# 7seg_clock_ver3.net
KiCad netlist of a schematic drawn in EAGLE
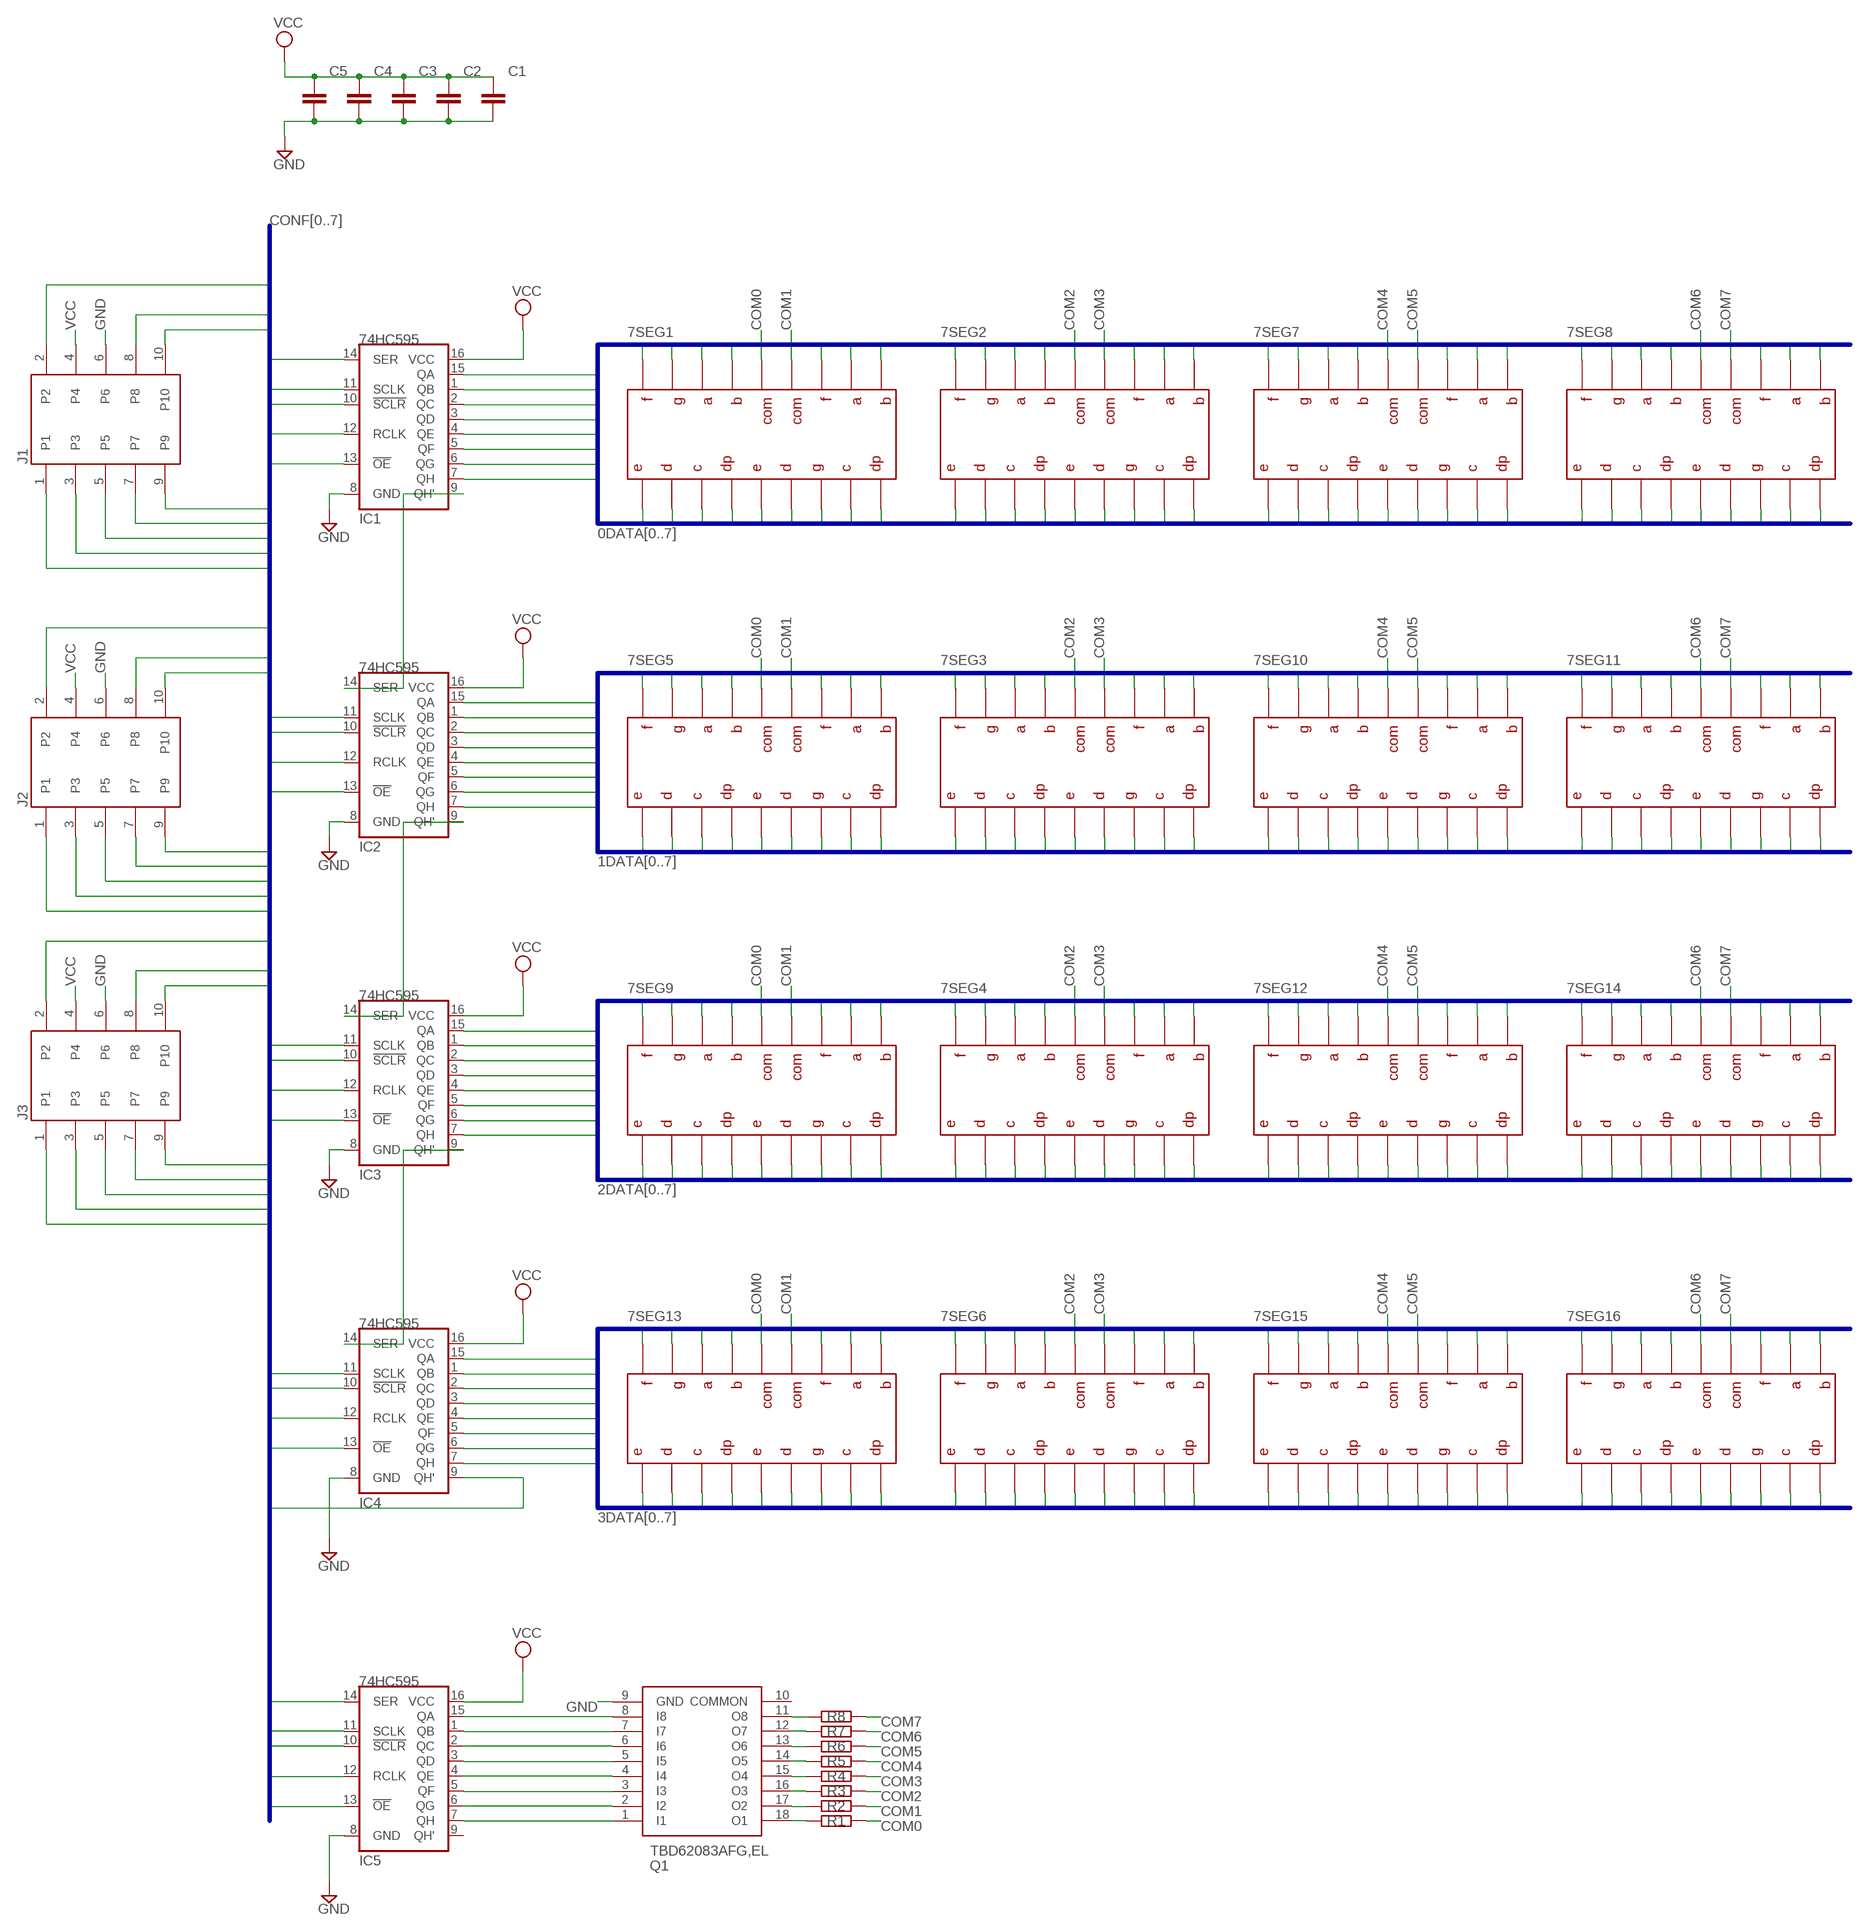
[diagram p0: schematic, sheet 1]

(export (version "E")
  (design (tool "Eeschema 10.0.6"))
  (components
    (comp (ref "7SEG1")
      (value "SL-3264")
      (footprint "eagle-import:SL-3264")
      (libsource (lib "eagle-import") (part "SL-3264"))
    )
    (comp (ref "7SEG2")
      (value "SL-3264")
      (footprint "eagle-import:SL-3264")
      (libsource (lib "eagle-import") (part "SL-3264"))
    )
    (comp (ref "7SEG3")
      (value "SL-3264")
      (footprint "eagle-import:SL-3264")
      (libsource (lib "eagle-import") (part "SL-3264"))
    )
    (comp (ref "7SEG4")
      (value "SL-3264")
      (footprint "eagle-import:SL-3264")
      (libsource (lib "eagle-import") (part "SL-3264"))
    )
    (comp (ref "7SEG5")
      (value "SL-3264")
      (footprint "eagle-import:SL-3264")
      (libsource (lib "eagle-import") (part "SL-3264"))
    )
    (comp (ref "7SEG6")
      (value "SL-3264")
      (footprint "eagle-import:SL-3264")
      (libsource (lib "eagle-import") (part "SL-3264"))
    )
    (comp (ref "7SEG7")
      (value "SL-3264")
      (footprint "eagle-import:SL-3264")
      (libsource (lib "eagle-import") (part "SL-3264"))
    )
    (comp (ref "7SEG8")
      (value "SL-3264")
      (footprint "eagle-import:SL-3264")
      (libsource (lib "eagle-import") (part "SL-3264"))
    )
    (comp (ref "7SEG9")
      (value "SL-3264")
      (footprint "eagle-import:SL-3264")
      (libsource (lib "eagle-import") (part "SL-3264"))
    )
    (comp (ref "7SEG10")
      (value "SL-3264")
      (footprint "eagle-import:SL-3264")
      (libsource (lib "eagle-import") (part "SL-3264"))
    )
    (comp (ref "7SEG11")
      (value "SL-3264")
      (footprint "eagle-import:SL-3264")
      (libsource (lib "eagle-import") (part "SL-3264"))
    )
    (comp (ref "7SEG12")
      (value "SL-3264")
      (footprint "eagle-import:SL-3264")
      (libsource (lib "eagle-import") (part "SL-3264"))
    )
    (comp (ref "7SEG13")
      (value "SL-3264")
      (footprint "eagle-import:SL-3264")
      (libsource (lib "eagle-import") (part "SL-3264"))
    )
    (comp (ref "7SEG14")
      (value "SL-3264")
      (footprint "eagle-import:SL-3264")
      (libsource (lib "eagle-import") (part "SL-3264"))
    )
    (comp (ref "7SEG15")
      (value "SL-3264")
      (footprint "eagle-import:SL-3264")
      (libsource (lib "eagle-import") (part "SL-3264"))
    )
    (comp (ref "7SEG16")
      (value "SL-3264")
      (footprint "eagle-import:SL-3264")
      (libsource (lib "eagle-import") (part "SL-3264"))
    )
    (comp (ref "C1")
      (value "C_CHIP-0603(1608-METRIC)")
      (footprint "eagle-import:CAPC1608X85")
      (libsource (lib "eagle-import") (part "CCHIP-0603(1608-METRIC)_"))
    )
    (comp (ref "C2")
      (value "C_CHIP-0603(1608-METRIC)")
      (footprint "eagle-import:CAPC1608X85")
      (libsource (lib "eagle-import") (part "CCHIP-0603(1608-METRIC)_"))
    )
    (comp (ref "C3")
      (value "C_CHIP-0603(1608-METRIC)")
      (footprint "eagle-import:CAPC1608X85")
      (libsource (lib "eagle-import") (part "CCHIP-0603(1608-METRIC)_"))
    )
    (comp (ref "C4")
      (value "C_CHIP-0603(1608-METRIC)")
      (footprint "eagle-import:CAPC1608X85")
      (libsource (lib "eagle-import") (part "CCHIP-0603(1608-METRIC)_"))
    )
    (comp (ref "C5")
      (value "C_CHIP-0603(1608-METRIC)")
      (footprint "eagle-import:CAPC1608X85")
      (libsource (lib "eagle-import") (part "CCHIP-0603(1608-METRIC)_"))
    )
    (comp (ref "IC1")
      (value "74HC595")
      (footprint "eagle-import:SO16")
      (fields (field (name "MF") "Nexperia"))
      (libsource (lib "eagle-import") (part "74HC595"))
    )
    (comp (ref "IC2")
      (value "74HC595")
      (footprint "eagle-import:SO16")
      (fields (field (name "MF") "Nexperia"))
      (libsource (lib "eagle-import") (part "74HC595"))
    )
    (comp (ref "IC3")
      (value "74HC595")
      (footprint "eagle-import:SO16")
      (fields (field (name "MF") "Nexperia"))
      (libsource (lib "eagle-import") (part "74HC595"))
    )
    (comp (ref "IC4")
      (value "74HC595")
      (footprint "eagle-import:SO16")
      (fields (field (name "MF") "Nexperia"))
      (libsource (lib "eagle-import") (part "74HC595"))
    )
    (comp (ref "IC5")
      (value "74HC595")
      (footprint "eagle-import:SO16")
      (fields (field (name "MF") "Nexperia"))
      (libsource (lib "eagle-import") (part "74HC595"))
    )
    (comp (ref "J1")
      (value "1241050-5")
      (footprint "eagle-import:TE_1241050-5")
      (fields (field (name "MF") "TE Connectivity"))
      (libsource (lib "eagle-import") (part "1241050-5"))
    )
    (comp (ref "J2")
      (value "1241050-5")
      (footprint "eagle-import:TE_1241050-5")
      (fields (field (name "MF") "TE Connectivity"))
      (libsource (lib "eagle-import") (part "1241050-5"))
    )
    (comp (ref "J3")
      (value "1241050-5")
      (footprint "eagle-import:TE_1241050-5")
      (fields (field (name "MF") "TE Connectivity"))
      (libsource (lib "eagle-import") (part "1241050-5"))
    )
    (comp (ref "Q1")
      (value "TBD62083AFG,EL")
      (footprint "eagle-import:SOIC127P1030X245-18N")
      (fields (field (name "MF") "Toshiba Semiconductor"))
      (libsource (lib "eagle-import") (part "TBD62083AFG,EL"))
    )
    (comp (ref "R1")
      (value "R_CHIP-0603(1608-METRIC)")
      (footprint "eagle-import:RESC1608X60")
      (libsource (lib "eagle-import") (part "RCHIP-0603(1608-METRIC)_"))
    )
    (comp (ref "R2")
      (value "R_CHIP-0603(1608-METRIC)")
      (footprint "eagle-import:RESC1608X60")
      (libsource (lib "eagle-import") (part "RCHIP-0603(1608-METRIC)_"))
    )
    (comp (ref "R3")
      (value "R_CHIP-0603(1608-METRIC)")
      (footprint "eagle-import:RESC1608X60")
      (libsource (lib "eagle-import") (part "RCHIP-0603(1608-METRIC)_"))
    )
    (comp (ref "R4")
      (value "R_CHIP-0603(1608-METRIC)")
      (footprint "eagle-import:RESC1608X60")
      (libsource (lib "eagle-import") (part "RCHIP-0603(1608-METRIC)_"))
    )
    (comp (ref "R5")
      (value "R_CHIP-0603(1608-METRIC)")
      (footprint "eagle-import:RESC1608X60")
      (libsource (lib "eagle-import") (part "RCHIP-0603(1608-METRIC)_"))
    )
    (comp (ref "R6")
      (value "R_CHIP-0603(1608-METRIC)")
      (footprint "eagle-import:RESC1608X60")
      (libsource (lib "eagle-import") (part "RCHIP-0603(1608-METRIC)_"))
    )
    (comp (ref "R7")
      (value "R_CHIP-0603(1608-METRIC)")
      (footprint "eagle-import:RESC1608X60")
      (libsource (lib "eagle-import") (part "RCHIP-0603(1608-METRIC)_"))
    )
    (comp (ref "R8")
      (value "R_CHIP-0603(1608-METRIC)")
      (footprint "eagle-import:RESC1608X60")
      (libsource (lib "eagle-import") (part "RCHIP-0603(1608-METRIC)_"))
    )
  )
  (nets
    (net (code "1") (name "/0DATA0") (class "Default")
      (node (ref "7SEG1") (pin "P$10") (pinfunction "P$10_P$10") (pintype "bidirectional"))
      (node (ref "7SEG1") (pin "P$15") (pinfunction "P$15_P$15") (pintype "bidirectional"))
      (node (ref "7SEG2") (pin "P$10") (pinfunction "P$10_P$10") (pintype "bidirectional"))
      (node (ref "7SEG2") (pin "P$15") (pinfunction "P$15_P$15") (pintype "bidirectional"))
      (node (ref "7SEG7") (pin "P$10") (pinfunction "P$10_P$10") (pintype "bidirectional"))
      (node (ref "7SEG7") (pin "P$15") (pinfunction "P$15_P$15") (pintype "bidirectional"))
      (node (ref "7SEG8") (pin "P$10") (pinfunction "P$10_P$10") (pintype "bidirectional"))
      (node (ref "7SEG8") (pin "P$15") (pinfunction "P$15_P$15") (pintype "bidirectional"))
      (node (ref "IC1") (pin "15") (pinfunction "QA_15") (pintype "tri_state"))
    )
    (net (code "2") (name "/0DATA1") (class "Default")
      (node (ref "7SEG1") (pin "P$12") (pinfunction "P$12_P$12") (pintype "bidirectional"))
      (node (ref "7SEG1") (pin "P$18") (pinfunction "P$18_P$18") (pintype "bidirectional"))
      (node (ref "7SEG2") (pin "P$12") (pinfunction "P$12_P$12") (pintype "bidirectional"))
      (node (ref "7SEG2") (pin "P$18") (pinfunction "P$18_P$18") (pintype "bidirectional"))
      (node (ref "7SEG7") (pin "P$12") (pinfunction "P$12_P$12") (pintype "bidirectional"))
      (node (ref "7SEG7") (pin "P$18") (pinfunction "P$18_P$18") (pintype "bidirectional"))
      (node (ref "7SEG8") (pin "P$12") (pinfunction "P$12_P$12") (pintype "bidirectional"))
      (node (ref "7SEG8") (pin "P$18") (pinfunction "P$18_P$18") (pintype "bidirectional"))
      (node (ref "IC1") (pin "1") (pinfunction "QB_1") (pintype "tri_state"))
    )
    (net (code "3") (name "/0DATA2") (class "Default")
      (node (ref "7SEG1") (pin "P$17") (pinfunction "P$17_P$17") (pintype "bidirectional"))
      (node (ref "7SEG1") (pin "P$7") (pinfunction "P$7_P$7") (pintype "bidirectional"))
      (node (ref "7SEG2") (pin "P$17") (pinfunction "P$17_P$17") (pintype "bidirectional"))
      (node (ref "7SEG2") (pin "P$7") (pinfunction "P$7_P$7") (pintype "bidirectional"))
      (node (ref "7SEG7") (pin "P$17") (pinfunction "P$17_P$17") (pintype "bidirectional"))
      (node (ref "7SEG7") (pin "P$7") (pinfunction "P$7_P$7") (pintype "bidirectional"))
      (node (ref "7SEG8") (pin "P$17") (pinfunction "P$17_P$17") (pintype "bidirectional"))
      (node (ref "7SEG8") (pin "P$7") (pinfunction "P$7_P$7") (pintype "bidirectional"))
      (node (ref "IC1") (pin "2") (pinfunction "QC_2") (pintype "tri_state"))
    )
    (net (code "4") (name "/0DATA3") (class "Default")
      (node (ref "7SEG1") (pin "P$11") (pinfunction "P$11_P$11") (pintype "bidirectional"))
      (node (ref "7SEG1") (pin "P$16") (pinfunction "P$16_P$16") (pintype "bidirectional"))
      (node (ref "7SEG2") (pin "P$11") (pinfunction "P$11_P$11") (pintype "bidirectional"))
      (node (ref "7SEG2") (pin "P$16") (pinfunction "P$16_P$16") (pintype "bidirectional"))
      (node (ref "7SEG7") (pin "P$11") (pinfunction "P$11_P$11") (pintype "bidirectional"))
      (node (ref "7SEG7") (pin "P$16") (pinfunction "P$16_P$16") (pintype "bidirectional"))
      (node (ref "7SEG8") (pin "P$11") (pinfunction "P$11_P$11") (pintype "bidirectional"))
      (node (ref "7SEG8") (pin "P$16") (pinfunction "P$16_P$16") (pintype "bidirectional"))
      (node (ref "IC1") (pin "3") (pinfunction "QD_3") (pintype "tri_state"))
    )
    (net (code "5") (name "/0DATA4") (class "Default")
      (node (ref "7SEG1") (pin "P$4") (pinfunction "P$4_P$4") (pintype "bidirectional"))
      (node (ref "7SEG1") (pin "P$9") (pinfunction "P$9_P$9") (pintype "bidirectional"))
      (node (ref "7SEG2") (pin "P$4") (pinfunction "P$4_P$4") (pintype "bidirectional"))
      (node (ref "7SEG2") (pin "P$9") (pinfunction "P$9_P$9") (pintype "bidirectional"))
      (node (ref "7SEG7") (pin "P$4") (pinfunction "P$4_P$4") (pintype "bidirectional"))
      (node (ref "7SEG7") (pin "P$9") (pinfunction "P$9_P$9") (pintype "bidirectional"))
      (node (ref "7SEG8") (pin "P$4") (pinfunction "P$4_P$4") (pintype "bidirectional"))
      (node (ref "7SEG8") (pin "P$9") (pinfunction "P$9_P$9") (pintype "bidirectional"))
      (node (ref "IC1") (pin "4") (pinfunction "QE_4") (pintype "tri_state"))
    )
    (net (code "6") (name "/0DATA5") (class "Default")
      (node (ref "7SEG1") (pin "P$3") (pinfunction "P$3_P$3") (pintype "bidirectional"))
      (node (ref "7SEG1") (pin "P$8") (pinfunction "P$8_P$8") (pintype "bidirectional"))
      (node (ref "7SEG2") (pin "P$3") (pinfunction "P$3_P$3") (pintype "bidirectional"))
      (node (ref "7SEG2") (pin "P$8") (pinfunction "P$8_P$8") (pintype "bidirectional"))
      (node (ref "7SEG7") (pin "P$3") (pinfunction "P$3_P$3") (pintype "bidirectional"))
      (node (ref "7SEG7") (pin "P$8") (pinfunction "P$8_P$8") (pintype "bidirectional"))
      (node (ref "7SEG8") (pin "P$3") (pinfunction "P$3_P$3") (pintype "bidirectional"))
      (node (ref "7SEG8") (pin "P$8") (pinfunction "P$8_P$8") (pintype "bidirectional"))
      (node (ref "IC1") (pin "5") (pinfunction "QF_5") (pintype "tri_state"))
    )
    (net (code "7") (name "/0DATA6") (class "Default")
      (node (ref "7SEG1") (pin "P$2") (pinfunction "P$2_P$2") (pintype "bidirectional"))
      (node (ref "7SEG1") (pin "P$6") (pinfunction "P$6_P$6") (pintype "bidirectional"))
      (node (ref "7SEG2") (pin "P$2") (pinfunction "P$2_P$2") (pintype "bidirectional"))
      (node (ref "7SEG2") (pin "P$6") (pinfunction "P$6_P$6") (pintype "bidirectional"))
      (node (ref "7SEG7") (pin "P$2") (pinfunction "P$2_P$2") (pintype "bidirectional"))
      (node (ref "7SEG7") (pin "P$6") (pinfunction "P$6_P$6") (pintype "bidirectional"))
      (node (ref "7SEG8") (pin "P$2") (pinfunction "P$2_P$2") (pintype "bidirectional"))
      (node (ref "7SEG8") (pin "P$6") (pinfunction "P$6_P$6") (pintype "bidirectional"))
      (node (ref "IC1") (pin "6") (pinfunction "QG_6") (pintype "tri_state"))
    )
    (net (code "8") (name "/0DATA7") (class "Default")
      (node (ref "7SEG1") (pin "P$1") (pinfunction "P$1_P$1") (pintype "bidirectional"))
      (node (ref "7SEG1") (pin "P$5") (pinfunction "P$5_P$5") (pintype "bidirectional"))
      (node (ref "7SEG2") (pin "P$1") (pinfunction "P$1_P$1") (pintype "bidirectional"))
      (node (ref "7SEG2") (pin "P$5") (pinfunction "P$5_P$5") (pintype "bidirectional"))
      (node (ref "7SEG7") (pin "P$1") (pinfunction "P$1_P$1") (pintype "bidirectional"))
      (node (ref "7SEG7") (pin "P$5") (pinfunction "P$5_P$5") (pintype "bidirectional"))
      (node (ref "7SEG8") (pin "P$1") (pinfunction "P$1_P$1") (pintype "bidirectional"))
      (node (ref "7SEG8") (pin "P$5") (pinfunction "P$5_P$5") (pintype "bidirectional"))
      (node (ref "IC1") (pin "7") (pinfunction "QH_7") (pintype "tri_state"))
    )
    (net (code "10") (name "/1DATA0") (class "Default")
      (node (ref "7SEG10") (pin "P$10") (pinfunction "P$10_P$10") (pintype "bidirectional"))
      (node (ref "7SEG10") (pin "P$15") (pinfunction "P$15_P$15") (pintype "bidirectional"))
      (node (ref "7SEG11") (pin "P$10") (pinfunction "P$10_P$10") (pintype "bidirectional"))
      (node (ref "7SEG11") (pin "P$15") (pinfunction "P$15_P$15") (pintype "bidirectional"))
      (node (ref "7SEG3") (pin "P$10") (pinfunction "P$10_P$10") (pintype "bidirectional"))
      (node (ref "7SEG3") (pin "P$15") (pinfunction "P$15_P$15") (pintype "bidirectional"))
      (node (ref "7SEG5") (pin "P$10") (pinfunction "P$10_P$10") (pintype "bidirectional"))
      (node (ref "7SEG5") (pin "P$15") (pinfunction "P$15_P$15") (pintype "bidirectional"))
      (node (ref "IC2") (pin "15") (pinfunction "QA_15") (pintype "tri_state"))
    )
    (net (code "11") (name "/1DATA1") (class "Default")
      (node (ref "7SEG10") (pin "P$12") (pinfunction "P$12_P$12") (pintype "bidirectional"))
      (node (ref "7SEG10") (pin "P$18") (pinfunction "P$18_P$18") (pintype "bidirectional"))
      (node (ref "7SEG11") (pin "P$12") (pinfunction "P$12_P$12") (pintype "bidirectional"))
      (node (ref "7SEG11") (pin "P$18") (pinfunction "P$18_P$18") (pintype "bidirectional"))
      (node (ref "7SEG3") (pin "P$12") (pinfunction "P$12_P$12") (pintype "bidirectional"))
      (node (ref "7SEG3") (pin "P$18") (pinfunction "P$18_P$18") (pintype "bidirectional"))
      (node (ref "7SEG5") (pin "P$12") (pinfunction "P$12_P$12") (pintype "bidirectional"))
      (node (ref "7SEG5") (pin "P$18") (pinfunction "P$18_P$18") (pintype "bidirectional"))
      (node (ref "IC2") (pin "1") (pinfunction "QB_1") (pintype "tri_state"))
    )
    (net (code "12") (name "/1DATA2") (class "Default")
      (node (ref "7SEG10") (pin "P$17") (pinfunction "P$17_P$17") (pintype "bidirectional"))
      (node (ref "7SEG10") (pin "P$7") (pinfunction "P$7_P$7") (pintype "bidirectional"))
      (node (ref "7SEG11") (pin "P$17") (pinfunction "P$17_P$17") (pintype "bidirectional"))
      (node (ref "7SEG11") (pin "P$7") (pinfunction "P$7_P$7") (pintype "bidirectional"))
      (node (ref "7SEG3") (pin "P$17") (pinfunction "P$17_P$17") (pintype "bidirectional"))
      (node (ref "7SEG3") (pin "P$7") (pinfunction "P$7_P$7") (pintype "bidirectional"))
      (node (ref "7SEG5") (pin "P$17") (pinfunction "P$17_P$17") (pintype "bidirectional"))
      (node (ref "7SEG5") (pin "P$7") (pinfunction "P$7_P$7") (pintype "bidirectional"))
      (node (ref "IC2") (pin "2") (pinfunction "QC_2") (pintype "tri_state"))
    )
    (net (code "13") (name "/1DATA3") (class "Default")
      (node (ref "7SEG10") (pin "P$11") (pinfunction "P$11_P$11") (pintype "bidirectional"))
      (node (ref "7SEG10") (pin "P$16") (pinfunction "P$16_P$16") (pintype "bidirectional"))
      (node (ref "7SEG11") (pin "P$11") (pinfunction "P$11_P$11") (pintype "bidirectional"))
      (node (ref "7SEG11") (pin "P$16") (pinfunction "P$16_P$16") (pintype "bidirectional"))
      (node (ref "7SEG3") (pin "P$11") (pinfunction "P$11_P$11") (pintype "bidirectional"))
      (node (ref "7SEG3") (pin "P$16") (pinfunction "P$16_P$16") (pintype "bidirectional"))
      (node (ref "7SEG5") (pin "P$11") (pinfunction "P$11_P$11") (pintype "bidirectional"))
      (node (ref "7SEG5") (pin "P$16") (pinfunction "P$16_P$16") (pintype "bidirectional"))
      (node (ref "IC2") (pin "3") (pinfunction "QD_3") (pintype "tri_state"))
    )
    (net (code "14") (name "/1DATA4") (class "Default")
      (node (ref "7SEG10") (pin "P$4") (pinfunction "P$4_P$4") (pintype "bidirectional"))
      (node (ref "7SEG10") (pin "P$9") (pinfunction "P$9_P$9") (pintype "bidirectional"))
      (node (ref "7SEG11") (pin "P$4") (pinfunction "P$4_P$4") (pintype "bidirectional"))
      (node (ref "7SEG11") (pin "P$9") (pinfunction "P$9_P$9") (pintype "bidirectional"))
      (node (ref "7SEG3") (pin "P$4") (pinfunction "P$4_P$4") (pintype "bidirectional"))
      (node (ref "7SEG3") (pin "P$9") (pinfunction "P$9_P$9") (pintype "bidirectional"))
      (node (ref "7SEG5") (pin "P$4") (pinfunction "P$4_P$4") (pintype "bidirectional"))
      (node (ref "7SEG5") (pin "P$9") (pinfunction "P$9_P$9") (pintype "bidirectional"))
      (node (ref "IC2") (pin "4") (pinfunction "QE_4") (pintype "tri_state"))
    )
    (net (code "15") (name "/1DATA5") (class "Default")
      (node (ref "7SEG10") (pin "P$3") (pinfunction "P$3_P$3") (pintype "bidirectional"))
      (node (ref "7SEG10") (pin "P$8") (pinfunction "P$8_P$8") (pintype "bidirectional"))
      (node (ref "7SEG11") (pin "P$3") (pinfunction "P$3_P$3") (pintype "bidirectional"))
      (node (ref "7SEG11") (pin "P$8") (pinfunction "P$8_P$8") (pintype "bidirectional"))
      (node (ref "7SEG3") (pin "P$3") (pinfunction "P$3_P$3") (pintype "bidirectional"))
      (node (ref "7SEG3") (pin "P$8") (pinfunction "P$8_P$8") (pintype "bidirectional"))
      (node (ref "7SEG5") (pin "P$3") (pinfunction "P$3_P$3") (pintype "bidirectional"))
      (node (ref "7SEG5") (pin "P$8") (pinfunction "P$8_P$8") (pintype "bidirectional"))
      (node (ref "IC2") (pin "5") (pinfunction "QF_5") (pintype "tri_state"))
    )
    (net (code "16") (name "/1DATA6") (class "Default")
      (node (ref "7SEG10") (pin "P$2") (pinfunction "P$2_P$2") (pintype "bidirectional"))
      (node (ref "7SEG10") (pin "P$6") (pinfunction "P$6_P$6") (pintype "bidirectional"))
      (node (ref "7SEG11") (pin "P$2") (pinfunction "P$2_P$2") (pintype "bidirectional"))
      (node (ref "7SEG11") (pin "P$6") (pinfunction "P$6_P$6") (pintype "bidirectional"))
      (node (ref "7SEG3") (pin "P$2") (pinfunction "P$2_P$2") (pintype "bidirectional"))
      (node (ref "7SEG3") (pin "P$6") (pinfunction "P$6_P$6") (pintype "bidirectional"))
      (node (ref "7SEG5") (pin "P$2") (pinfunction "P$2_P$2") (pintype "bidirectional"))
      (node (ref "7SEG5") (pin "P$6") (pinfunction "P$6_P$6") (pintype "bidirectional"))
      (node (ref "IC2") (pin "6") (pinfunction "QG_6") (pintype "tri_state"))
    )
    (net (code "17") (name "/1DATA7") (class "Default")
      (node (ref "7SEG10") (pin "P$1") (pinfunction "P$1_P$1") (pintype "bidirectional"))
      (node (ref "7SEG10") (pin "P$5") (pinfunction "P$5_P$5") (pintype "bidirectional"))
      (node (ref "7SEG11") (pin "P$1") (pinfunction "P$1_P$1") (pintype "bidirectional"))
      (node (ref "7SEG11") (pin "P$5") (pinfunction "P$5_P$5") (pintype "bidirectional"))
      (node (ref "7SEG3") (pin "P$1") (pinfunction "P$1_P$1") (pintype "bidirectional"))
      (node (ref "7SEG3") (pin "P$5") (pinfunction "P$5_P$5") (pintype "bidirectional"))
      (node (ref "7SEG5") (pin "P$1") (pinfunction "P$1_P$1") (pintype "bidirectional"))
      (node (ref "7SEG5") (pin "P$5") (pinfunction "P$5_P$5") (pintype "bidirectional"))
      (node (ref "IC2") (pin "7") (pinfunction "QH_7") (pintype "tri_state"))
    )
    (net (code "19") (name "/2DATA0") (class "Default")
      (node (ref "7SEG12") (pin "P$10") (pinfunction "P$10_P$10") (pintype "bidirectional"))
      (node (ref "7SEG12") (pin "P$15") (pinfunction "P$15_P$15") (pintype "bidirectional"))
      (node (ref "7SEG14") (pin "P$10") (pinfunction "P$10_P$10") (pintype "bidirectional"))
      (node (ref "7SEG14") (pin "P$15") (pinfunction "P$15_P$15") (pintype "bidirectional"))
      (node (ref "7SEG4") (pin "P$10") (pinfunction "P$10_P$10") (pintype "bidirectional"))
      (node (ref "7SEG4") (pin "P$15") (pinfunction "P$15_P$15") (pintype "bidirectional"))
      (node (ref "7SEG9") (pin "P$10") (pinfunction "P$10_P$10") (pintype "bidirectional"))
      (node (ref "7SEG9") (pin "P$15") (pinfunction "P$15_P$15") (pintype "bidirectional"))
      (node (ref "IC3") (pin "15") (pinfunction "QA_15") (pintype "tri_state"))
    )
    (net (code "20") (name "/2DATA1") (class "Default")
      (node (ref "7SEG12") (pin "P$12") (pinfunction "P$12_P$12") (pintype "bidirectional"))
      (node (ref "7SEG12") (pin "P$18") (pinfunction "P$18_P$18") (pintype "bidirectional"))
      (node (ref "7SEG14") (pin "P$12") (pinfunction "P$12_P$12") (pintype "bidirectional"))
      (node (ref "7SEG14") (pin "P$18") (pinfunction "P$18_P$18") (pintype "bidirectional"))
      (node (ref "7SEG4") (pin "P$12") (pinfunction "P$12_P$12") (pintype "bidirectional"))
      (node (ref "7SEG4") (pin "P$18") (pinfunction "P$18_P$18") (pintype "bidirectional"))
      (node (ref "7SEG9") (pin "P$12") (pinfunction "P$12_P$12") (pintype "bidirectional"))
      (node (ref "7SEG9") (pin "P$18") (pinfunction "P$18_P$18") (pintype "bidirectional"))
      (node (ref "IC3") (pin "1") (pinfunction "QB_1") (pintype "tri_state"))
    )
    (net (code "21") (name "/2DATA2") (class "Default")
      (node (ref "7SEG12") (pin "P$17") (pinfunction "P$17_P$17") (pintype "bidirectional"))
      (node (ref "7SEG12") (pin "P$7") (pinfunction "P$7_P$7") (pintype "bidirectional"))
      (node (ref "7SEG14") (pin "P$17") (pinfunction "P$17_P$17") (pintype "bidirectional"))
      (node (ref "7SEG14") (pin "P$7") (pinfunction "P$7_P$7") (pintype "bidirectional"))
      (node (ref "7SEG4") (pin "P$17") (pinfunction "P$17_P$17") (pintype "bidirectional"))
      (node (ref "7SEG4") (pin "P$7") (pinfunction "P$7_P$7") (pintype "bidirectional"))
      (node (ref "7SEG9") (pin "P$17") (pinfunction "P$17_P$17") (pintype "bidirectional"))
      (node (ref "7SEG9") (pin "P$7") (pinfunction "P$7_P$7") (pintype "bidirectional"))
      (node (ref "IC3") (pin "2") (pinfunction "QC_2") (pintype "tri_state"))
    )
    (net (code "22") (name "/2DATA3") (class "Default")
      (node (ref "7SEG12") (pin "P$11") (pinfunction "P$11_P$11") (pintype "bidirectional"))
      (node (ref "7SEG12") (pin "P$16") (pinfunction "P$16_P$16") (pintype "bidirectional"))
      (node (ref "7SEG14") (pin "P$11") (pinfunction "P$11_P$11") (pintype "bidirectional"))
      (node (ref "7SEG14") (pin "P$16") (pinfunction "P$16_P$16") (pintype "bidirectional"))
      (node (ref "7SEG4") (pin "P$11") (pinfunction "P$11_P$11") (pintype "bidirectional"))
      (node (ref "7SEG4") (pin "P$16") (pinfunction "P$16_P$16") (pintype "bidirectional"))
      (node (ref "7SEG9") (pin "P$11") (pinfunction "P$11_P$11") (pintype "bidirectional"))
      (node (ref "7SEG9") (pin "P$16") (pinfunction "P$16_P$16") (pintype "bidirectional"))
      (node (ref "IC3") (pin "3") (pinfunction "QD_3") (pintype "tri_state"))
    )
    (net (code "23") (name "/2DATA4") (class "Default")
      (node (ref "7SEG12") (pin "P$4") (pinfunction "P$4_P$4") (pintype "bidirectional"))
      (node (ref "7SEG12") (pin "P$9") (pinfunction "P$9_P$9") (pintype "bidirectional"))
      (node (ref "7SEG14") (pin "P$4") (pinfunction "P$4_P$4") (pintype "bidirectional"))
      (node (ref "7SEG14") (pin "P$9") (pinfunction "P$9_P$9") (pintype "bidirectional"))
      (node (ref "7SEG4") (pin "P$4") (pinfunction "P$4_P$4") (pintype "bidirectional"))
      (node (ref "7SEG4") (pin "P$9") (pinfunction "P$9_P$9") (pintype "bidirectional"))
      (node (ref "7SEG9") (pin "P$4") (pinfunction "P$4_P$4") (pintype "bidirectional"))
      (node (ref "7SEG9") (pin "P$9") (pinfunction "P$9_P$9") (pintype "bidirectional"))
      (node (ref "IC3") (pin "4") (pinfunction "QE_4") (pintype "tri_state"))
    )
    (net (code "24") (name "/2DATA5") (class "Default")
      (node (ref "7SEG12") (pin "P$3") (pinfunction "P$3_P$3") (pintype "bidirectional"))
      (node (ref "7SEG12") (pin "P$8") (pinfunction "P$8_P$8") (pintype "bidirectional"))
      (node (ref "7SEG14") (pin "P$3") (pinfunction "P$3_P$3") (pintype "bidirectional"))
      (node (ref "7SEG14") (pin "P$8") (pinfunction "P$8_P$8") (pintype "bidirectional"))
      (node (ref "7SEG4") (pin "P$3") (pinfunction "P$3_P$3") (pintype "bidirectional"))
      (node (ref "7SEG4") (pin "P$8") (pinfunction "P$8_P$8") (pintype "bidirectional"))
      (node (ref "7SEG9") (pin "P$3") (pinfunction "P$3_P$3") (pintype "bidirectional"))
      (node (ref "7SEG9") (pin "P$8") (pinfunction "P$8_P$8") (pintype "bidirectional"))
      (node (ref "IC3") (pin "5") (pinfunction "QF_5") (pintype "tri_state"))
    )
    (net (code "25") (name "/2DATA6") (class "Default")
      (node (ref "7SEG12") (pin "P$2") (pinfunction "P$2_P$2") (pintype "bidirectional"))
      (node (ref "7SEG12") (pin "P$6") (pinfunction "P$6_P$6") (pintype "bidirectional"))
      (node (ref "7SEG14") (pin "P$2") (pinfunction "P$2_P$2") (pintype "bidirectional"))
      (node (ref "7SEG14") (pin "P$6") (pinfunction "P$6_P$6") (pintype "bidirectional"))
      (node (ref "7SEG4") (pin "P$2") (pinfunction "P$2_P$2") (pintype "bidirectional"))
      (node (ref "7SEG4") (pin "P$6") (pinfunction "P$6_P$6") (pintype "bidirectional"))
      (node (ref "7SEG9") (pin "P$2") (pinfunction "P$2_P$2") (pintype "bidirectional"))
      (node (ref "7SEG9") (pin "P$6") (pinfunction "P$6_P$6") (pintype "bidirectional"))
      (node (ref "IC3") (pin "6") (pinfunction "QG_6") (pintype "tri_state"))
    )
    (net (code "26") (name "/2DATA7") (class "Default")
      (node (ref "7SEG12") (pin "P$1") (pinfunction "P$1_P$1") (pintype "bidirectional"))
      (node (ref "7SEG12") (pin "P$5") (pinfunction "P$5_P$5") (pintype "bidirectional"))
      (node (ref "7SEG14") (pin "P$1") (pinfunction "P$1_P$1") (pintype "bidirectional"))
      (node (ref "7SEG14") (pin "P$5") (pinfunction "P$5_P$5") (pintype "bidirectional"))
      (node (ref "7SEG4") (pin "P$1") (pinfunction "P$1_P$1") (pintype "bidirectional"))
      (node (ref "7SEG4") (pin "P$5") (pinfunction "P$5_P$5") (pintype "bidirectional"))
      (node (ref "7SEG9") (pin "P$1") (pinfunction "P$1_P$1") (pintype "bidirectional"))
      (node (ref "7SEG9") (pin "P$5") (pinfunction "P$5_P$5") (pintype "bidirectional"))
      (node (ref "IC3") (pin "7") (pinfunction "QH_7") (pintype "tri_state"))
    )
    (net (code "28") (name "/3DATA0") (class "Default")
      (node (ref "7SEG13") (pin "P$10") (pinfunction "P$10_P$10") (pintype "bidirectional"))
      (node (ref "7SEG13") (pin "P$15") (pinfunction "P$15_P$15") (pintype "bidirectional"))
      (node (ref "7SEG15") (pin "P$10") (pinfunction "P$10_P$10") (pintype "bidirectional"))
      (node (ref "7SEG15") (pin "P$15") (pinfunction "P$15_P$15") (pintype "bidirectional"))
      (node (ref "7SEG16") (pin "P$10") (pinfunction "P$10_P$10") (pintype "bidirectional"))
      (node (ref "7SEG16") (pin "P$15") (pinfunction "P$15_P$15") (pintype "bidirectional"))
      (node (ref "7SEG6") (pin "P$10") (pinfunction "P$10_P$10") (pintype "bidirectional"))
      (node (ref "7SEG6") (pin "P$15") (pinfunction "P$15_P$15") (pintype "bidirectional"))
      (node (ref "IC4") (pin "15") (pinfunction "QA_15") (pintype "tri_state"))
    )
    (net (code "29") (name "/3DATA1") (class "Default")
      (node (ref "7SEG13") (pin "P$12") (pinfunction "P$12_P$12") (pintype "bidirectional"))
      (node (ref "7SEG13") (pin "P$18") (pinfunction "P$18_P$18") (pintype "bidirectional"))
      (node (ref "7SEG15") (pin "P$12") (pinfunction "P$12_P$12") (pintype "bidirectional"))
      (node (ref "7SEG15") (pin "P$18") (pinfunction "P$18_P$18") (pintype "bidirectional"))
      (node (ref "7SEG16") (pin "P$12") (pinfunction "P$12_P$12") (pintype "bidirectional"))
      (node (ref "7SEG16") (pin "P$18") (pinfunction "P$18_P$18") (pintype "bidirectional"))
      (node (ref "7SEG6") (pin "P$12") (pinfunction "P$12_P$12") (pintype "bidirectional"))
      (node (ref "7SEG6") (pin "P$18") (pinfunction "P$18_P$18") (pintype "bidirectional"))
      (node (ref "IC4") (pin "1") (pinfunction "QB_1") (pintype "tri_state"))
    )
    (net (code "30") (name "/3DATA2") (class "Default")
      (node (ref "7SEG13") (pin "P$17") (pinfunction "P$17_P$17") (pintype "bidirectional"))
      (node (ref "7SEG13") (pin "P$7") (pinfunction "P$7_P$7") (pintype "bidirectional"))
      (node (ref "7SEG15") (pin "P$17") (pinfunction "P$17_P$17") (pintype "bidirectional"))
      (node (ref "7SEG15") (pin "P$7") (pinfunction "P$7_P$7") (pintype "bidirectional"))
      (node (ref "7SEG16") (pin "P$17") (pinfunction "P$17_P$17") (pintype "bidirectional"))
      (node (ref "7SEG16") (pin "P$7") (pinfunction "P$7_P$7") (pintype "bidirectional"))
      (node (ref "7SEG6") (pin "P$17") (pinfunction "P$17_P$17") (pintype "bidirectional"))
      (node (ref "7SEG6") (pin "P$7") (pinfunction "P$7_P$7") (pintype "bidirectional"))
      (node (ref "IC4") (pin "2") (pinfunction "QC_2") (pintype "tri_state"))
    )
    (net (code "31") (name "/3DATA3") (class "Default")
      (node (ref "7SEG13") (pin "P$11") (pinfunction "P$11_P$11") (pintype "bidirectional"))
      (node (ref "7SEG13") (pin "P$16") (pinfunction "P$16_P$16") (pintype "bidirectional"))
      (node (ref "7SEG15") (pin "P$11") (pinfunction "P$11_P$11") (pintype "bidirectional"))
      (node (ref "7SEG15") (pin "P$16") (pinfunction "P$16_P$16") (pintype "bidirectional"))
      (node (ref "7SEG16") (pin "P$11") (pinfunction "P$11_P$11") (pintype "bidirectional"))
      (node (ref "7SEG16") (pin "P$16") (pinfunction "P$16_P$16") (pintype "bidirectional"))
      (node (ref "7SEG6") (pin "P$11") (pinfunction "P$11_P$11") (pintype "bidirectional"))
      (node (ref "7SEG6") (pin "P$16") (pinfunction "P$16_P$16") (pintype "bidirectional"))
      (node (ref "IC4") (pin "3") (pinfunction "QD_3") (pintype "tri_state"))
    )
    (net (code "32") (name "/3DATA4") (class "Default")
      (node (ref "7SEG13") (pin "P$4") (pinfunction "P$4_P$4") (pintype "bidirectional"))
      (node (ref "7SEG13") (pin "P$9") (pinfunction "P$9_P$9") (pintype "bidirectional"))
      (node (ref "7SEG15") (pin "P$4") (pinfunction "P$4_P$4") (pintype "bidirectional"))
      (node (ref "7SEG15") (pin "P$9") (pinfunction "P$9_P$9") (pintype "bidirectional"))
      (node (ref "7SEG16") (pin "P$4") (pinfunction "P$4_P$4") (pintype "bidirectional"))
      (node (ref "7SEG16") (pin "P$9") (pinfunction "P$9_P$9") (pintype "bidirectional"))
      (node (ref "7SEG6") (pin "P$4") (pinfunction "P$4_P$4") (pintype "bidirectional"))
      (node (ref "7SEG6") (pin "P$9") (pinfunction "P$9_P$9") (pintype "bidirectional"))
      (node (ref "IC4") (pin "4") (pinfunction "QE_4") (pintype "tri_state"))
    )
    (net (code "33") (name "/3DATA5") (class "Default")
      (node (ref "7SEG13") (pin "P$3") (pinfunction "P$3_P$3") (pintype "bidirectional"))
      (node (ref "7SEG13") (pin "P$8") (pinfunction "P$8_P$8") (pintype "bidirectional"))
      (node (ref "7SEG15") (pin "P$3") (pinfunction "P$3_P$3") (pintype "bidirectional"))
      (node (ref "7SEG15") (pin "P$8") (pinfunction "P$8_P$8") (pintype "bidirectional"))
      (node (ref "7SEG16") (pin "P$3") (pinfunction "P$3_P$3") (pintype "bidirectional"))
      (node (ref "7SEG16") (pin "P$8") (pinfunction "P$8_P$8") (pintype "bidirectional"))
      (node (ref "7SEG6") (pin "P$3") (pinfunction "P$3_P$3") (pintype "bidirectional"))
      (node (ref "7SEG6") (pin "P$8") (pinfunction "P$8_P$8") (pintype "bidirectional"))
      (node (ref "IC4") (pin "5") (pinfunction "QF_5") (pintype "tri_state"))
    )
    (net (code "34") (name "/3DATA6") (class "Default")
      (node (ref "7SEG13") (pin "P$2") (pinfunction "P$2_P$2") (pintype "bidirectional"))
      (node (ref "7SEG13") (pin "P$6") (pinfunction "P$6_P$6") (pintype "bidirectional"))
      (node (ref "7SEG15") (pin "P$2") (pinfunction "P$2_P$2") (pintype "bidirectional"))
      (node (ref "7SEG15") (pin "P$6") (pinfunction "P$6_P$6") (pintype "bidirectional"))
      (node (ref "7SEG16") (pin "P$2") (pinfunction "P$2_P$2") (pintype "bidirectional"))
      (node (ref "7SEG16") (pin "P$6") (pinfunction "P$6_P$6") (pintype "bidirectional"))
      (node (ref "7SEG6") (pin "P$2") (pinfunction "P$2_P$2") (pintype "bidirectional"))
      (node (ref "7SEG6") (pin "P$6") (pinfunction "P$6_P$6") (pintype "bidirectional"))
      (node (ref "IC4") (pin "6") (pinfunction "QG_6") (pintype "tri_state"))
    )
    (net (code "35") (name "/3DATA7") (class "Default")
      (node (ref "7SEG13") (pin "P$1") (pinfunction "P$1_P$1") (pintype "bidirectional"))
      (node (ref "7SEG13") (pin "P$5") (pinfunction "P$5_P$5") (pintype "bidirectional"))
      (node (ref "7SEG15") (pin "P$1") (pinfunction "P$1_P$1") (pintype "bidirectional"))
      (node (ref "7SEG15") (pin "P$5") (pinfunction "P$5_P$5") (pintype "bidirectional"))
      (node (ref "7SEG16") (pin "P$1") (pinfunction "P$1_P$1") (pintype "bidirectional"))
      (node (ref "7SEG16") (pin "P$5") (pinfunction "P$5_P$5") (pintype "bidirectional"))
      (node (ref "7SEG6") (pin "P$1") (pinfunction "P$1_P$1") (pintype "bidirectional"))
      (node (ref "7SEG6") (pin "P$5") (pinfunction "P$5_P$5") (pintype "bidirectional"))
      (node (ref "IC4") (pin "7") (pinfunction "QH_7") (pintype "tri_state"))
    )
    (net (code "37") (name "/COM0") (class "Default")
      (node (ref "7SEG1") (pin "P$14") (pinfunction "P$14_P$14") (pintype "power_in"))
      (node (ref "7SEG13") (pin "P$14") (pinfunction "P$14_P$14") (pintype "power_in"))
      (node (ref "7SEG5") (pin "P$14") (pinfunction "P$14_P$14") (pintype "power_in"))
      (node (ref "7SEG9") (pin "P$14") (pinfunction "P$14_P$14") (pintype "power_in"))
      (node (ref "R1") (pin "2") (pinfunction "2_2") (pintype "passive"))
    )
    (net (code "38") (name "/COM1") (class "Default")
      (node (ref "7SEG1") (pin "P$13") (pinfunction "P$13_P$13") (pintype "power_in"))
      (node (ref "7SEG13") (pin "P$13") (pinfunction "P$13_P$13") (pintype "power_in"))
      (node (ref "7SEG5") (pin "P$13") (pinfunction "P$13_P$13") (pintype "power_in"))
      (node (ref "7SEG9") (pin "P$13") (pinfunction "P$13_P$13") (pintype "power_in"))
      (node (ref "R2") (pin "2") (pinfunction "2_2") (pintype "passive"))
    )
    (net (code "39") (name "/COM2") (class "Default")
      (node (ref "7SEG2") (pin "P$14") (pinfunction "P$14_P$14") (pintype "power_in"))
      (node (ref "7SEG3") (pin "P$14") (pinfunction "P$14_P$14") (pintype "power_in"))
      (node (ref "7SEG4") (pin "P$14") (pinfunction "P$14_P$14") (pintype "power_in"))
      (node (ref "7SEG6") (pin "P$14") (pinfunction "P$14_P$14") (pintype "power_in"))
      (node (ref "R3") (pin "2") (pinfunction "2_2") (pintype "passive"))
    )
    (net (code "40") (name "/COM3") (class "Default")
      (node (ref "7SEG2") (pin "P$13") (pinfunction "P$13_P$13") (pintype "power_in"))
      (node (ref "7SEG3") (pin "P$13") (pinfunction "P$13_P$13") (pintype "power_in"))
      (node (ref "7SEG4") (pin "P$13") (pinfunction "P$13_P$13") (pintype "power_in"))
      (node (ref "7SEG6") (pin "P$13") (pinfunction "P$13_P$13") (pintype "power_in"))
      (node (ref "R4") (pin "2") (pinfunction "2_2") (pintype "passive"))
    )
    (net (code "41") (name "/COM4") (class "Default")
      (node (ref "7SEG10") (pin "P$14") (pinfunction "P$14_P$14") (pintype "power_in"))
      (node (ref "7SEG12") (pin "P$14") (pinfunction "P$14_P$14") (pintype "power_in"))
      (node (ref "7SEG15") (pin "P$14") (pinfunction "P$14_P$14") (pintype "power_in"))
      (node (ref "7SEG7") (pin "P$14") (pinfunction "P$14_P$14") (pintype "power_in"))
      (node (ref "R5") (pin "2") (pinfunction "2_2") (pintype "passive"))
    )
    (net (code "42") (name "/COM5") (class "Default")
      (node (ref "7SEG10") (pin "P$13") (pinfunction "P$13_P$13") (pintype "power_in"))
      (node (ref "7SEG12") (pin "P$13") (pinfunction "P$13_P$13") (pintype "power_in"))
      (node (ref "7SEG15") (pin "P$13") (pinfunction "P$13_P$13") (pintype "power_in"))
      (node (ref "7SEG7") (pin "P$13") (pinfunction "P$13_P$13") (pintype "power_in"))
      (node (ref "R6") (pin "2") (pinfunction "2_2") (pintype "passive"))
    )
    (net (code "43") (name "/COM6") (class "Default")
      (node (ref "7SEG11") (pin "P$14") (pinfunction "P$14_P$14") (pintype "power_in"))
      (node (ref "7SEG14") (pin "P$14") (pinfunction "P$14_P$14") (pintype "power_in"))
      (node (ref "7SEG16") (pin "P$14") (pinfunction "P$14_P$14") (pintype "power_in"))
      (node (ref "7SEG8") (pin "P$14") (pinfunction "P$14_P$14") (pintype "power_in"))
      (node (ref "R7") (pin "2") (pinfunction "2_2") (pintype "passive"))
    )
    (net (code "44") (name "/COM7") (class "Default")
      (node (ref "7SEG11") (pin "P$13") (pinfunction "P$13_P$13") (pintype "power_in"))
      (node (ref "7SEG14") (pin "P$13") (pinfunction "P$13_P$13") (pintype "power_in"))
      (node (ref "7SEG16") (pin "P$13") (pinfunction "P$13_P$13") (pintype "power_in"))
      (node (ref "7SEG8") (pin "P$13") (pinfunction "P$13_P$13") (pintype "power_in"))
      (node (ref "R8") (pin "2") (pinfunction "2_2") (pintype "passive"))
    )
    (net (code "45") (name "/CONF0") (class "Default")
      (node (ref "IC1") (pin "14") (pinfunction "SER_14") (pintype "input"))
      (node (ref "J1") (pin "1") (pinfunction "P1_1") (pintype "passive"))
      (node (ref "J2") (pin "1") (pinfunction "P1_1") (pintype "passive"))
      (node (ref "J3") (pin "1") (pinfunction "P1_1") (pintype "passive"))
    )
    (net (code "46") (name "/CONF1") (class "Default")
      (node (ref "IC1") (pin "11") (pinfunction "SCLK_11") (pintype "input"))
      (node (ref "IC2") (pin "11") (pinfunction "SCLK_11") (pintype "input"))
      (node (ref "IC3") (pin "11") (pinfunction "SCLK_11") (pintype "input"))
      (node (ref "IC4") (pin "11") (pinfunction "SCLK_11") (pintype "input"))
      (node (ref "IC5") (pin "11") (pinfunction "SCLK_11") (pintype "input"))
      (node (ref "J1") (pin "7") (pinfunction "P7_7") (pintype "passive"))
      (node (ref "J2") (pin "7") (pinfunction "P7_7") (pintype "passive"))
      (node (ref "J3") (pin "7") (pinfunction "P7_7") (pintype "passive"))
    )
    (net (code "47") (name "/CONF2") (class "Default")
      (node (ref "IC1") (pin "10") (pinfunction "~{SCLR}_10") (pintype "input"))
      (node (ref "IC2") (pin "10") (pinfunction "~{SCLR}_10") (pintype "input"))
      (node (ref "IC3") (pin "10") (pinfunction "~{SCLR}_10") (pintype "input"))
      (node (ref "IC4") (pin "10") (pinfunction "~{SCLR}_10") (pintype "input"))
      (node (ref "IC5") (pin "10") (pinfunction "~{SCLR}_10") (pintype "input"))
      (node (ref "J1") (pin "9") (pinfunction "P9_9") (pintype "passive"))
      (node (ref "J2") (pin "9") (pinfunction "P9_9") (pintype "passive"))
      (node (ref "J3") (pin "9") (pinfunction "P9_9") (pintype "passive"))
    )
    (net (code "48") (name "/CONF3") (class "Default")
      (node (ref "IC1") (pin "12") (pinfunction "RCLK_12") (pintype "input"))
      (node (ref "IC2") (pin "12") (pinfunction "RCLK_12") (pintype "input"))
      (node (ref "IC3") (pin "12") (pinfunction "RCLK_12") (pintype "input"))
      (node (ref "IC4") (pin "12") (pinfunction "RCLK_12") (pintype "input"))
      (node (ref "J1") (pin "5") (pinfunction "P5_5") (pintype "passive"))
      (node (ref "J2") (pin "5") (pinfunction "P5_5") (pintype "passive"))
      (node (ref "J3") (pin "5") (pinfunction "P5_5") (pintype "passive"))
    )
    (net (code "49") (name "/CONF4") (class "Default")
      (node (ref "IC1") (pin "13") (pinfunction "~{OE}_13") (pintype "input"))
      (node (ref "IC2") (pin "13") (pinfunction "~{OE}_13") (pintype "input"))
      (node (ref "IC3") (pin "13") (pinfunction "~{OE}_13") (pintype "input"))
      (node (ref "IC4") (pin "13") (pinfunction "~{OE}_13") (pintype "input"))
      (node (ref "IC5") (pin "13") (pinfunction "~{OE}_13") (pintype "input"))
      (node (ref "J1") (pin "3") (pinfunction "P3_3") (pintype "passive"))
      (node (ref "J2") (pin "3") (pinfunction "P3_3") (pintype "passive"))
      (node (ref "J3") (pin "3") (pinfunction "P3_3") (pintype "passive"))
    )
    (net (code "50") (name "/CONF5") (class "Default")
      (node (ref "IC4") (pin "9") (pinfunction "QH'_9") (pintype "tri_state"))
      (node (ref "J1") (pin "10") (pinfunction "P10_10") (pintype "passive"))
      (node (ref "J2") (pin "10") (pinfunction "P10_10") (pintype "passive"))
      (node (ref "J3") (pin "10") (pinfunction "P10_10") (pintype "passive"))
    )
    (net (code "51") (name "/CONF6") (class "Default")
      (node (ref "IC5") (pin "14") (pinfunction "SER_14") (pintype "input"))
      (node (ref "J1") (pin "8") (pinfunction "P8_8") (pintype "passive"))
      (node (ref "J2") (pin "8") (pinfunction "P8_8") (pintype "passive"))
      (node (ref "J3") (pin "8") (pinfunction "P8_8") (pintype "passive"))
    )
    (net (code "52") (name "/CONF7") (class "Default")
      (node (ref "IC5") (pin "12") (pinfunction "RCLK_12") (pintype "input"))
      (node (ref "J1") (pin "2") (pinfunction "P2_2") (pintype "passive"))
      (node (ref "J2") (pin "2") (pinfunction "P2_2") (pintype "passive"))
      (node (ref "J3") (pin "2") (pinfunction "P2_2") (pintype "passive"))
    )
    (net (code "54") (name "GND") (class "Default")
      (node (ref "C1") (pin "2") (pinfunction "2_2") (pintype "passive"))
      (node (ref "C2") (pin "2") (pinfunction "2_2") (pintype "passive"))
      (node (ref "C3") (pin "2") (pinfunction "2_2") (pintype "passive"))
      (node (ref "C4") (pin "2") (pinfunction "2_2") (pintype "passive"))
      (node (ref "C5") (pin "2") (pinfunction "2_2") (pintype "passive"))
      (node (ref "IC1") (pin "8") (pinfunction "GND_8") (pintype "power_in"))
      (node (ref "IC2") (pin "8") (pinfunction "GND_8") (pintype "power_in"))
      (node (ref "IC3") (pin "8") (pinfunction "GND_8") (pintype "power_in"))
      (node (ref "IC4") (pin "8") (pinfunction "GND_8") (pintype "power_in"))
      (node (ref "IC5") (pin "8") (pinfunction "GND_8") (pintype "power_in"))
      (node (ref "J1") (pin "6") (pinfunction "P6_6") (pintype "passive"))
      (node (ref "J2") (pin "6") (pinfunction "P6_6") (pintype "passive"))
      (node (ref "J3") (pin "6") (pinfunction "P6_6") (pintype "passive"))
      (node (ref "Q1") (pin "9") (pinfunction "GND_9") (pintype "bidirectional"))
    )
    (net (code "55") (name "Net-(IC1-QH')") (class "Default")
      (node (ref "IC1") (pin "9") (pinfunction "QH'_9") (pintype "tri_state"))
      (node (ref "IC2") (pin "14") (pinfunction "SER_14") (pintype "input"))
    )
    (net (code "56") (name "Net-(IC2-QH')") (class "Default")
      (node (ref "IC2") (pin "9") (pinfunction "QH'_9") (pintype "tri_state"))
      (node (ref "IC3") (pin "14") (pinfunction "SER_14") (pintype "input"))
    )
    (net (code "57") (name "Net-(IC3-QH')") (class "Default")
      (node (ref "IC3") (pin "9") (pinfunction "QH'_9") (pintype "tri_state"))
      (node (ref "IC4") (pin "14") (pinfunction "SER_14") (pintype "input"))
    )
    (net (code "58") (name "Net-(IC5-QA)") (class "Default")
      (node (ref "IC5") (pin "15") (pinfunction "QA_15") (pintype "tri_state"))
      (node (ref "Q1") (pin "8") (pinfunction "I8_8") (pintype "bidirectional"))
    )
    (net (code "59") (name "Net-(IC5-QB)") (class "Default")
      (node (ref "IC5") (pin "1") (pinfunction "QB_1") (pintype "tri_state"))
      (node (ref "Q1") (pin "7") (pinfunction "I7_7") (pintype "bidirectional"))
    )
    (net (code "60") (name "Net-(IC5-QC)") (class "Default")
      (node (ref "IC5") (pin "2") (pinfunction "QC_2") (pintype "tri_state"))
      (node (ref "Q1") (pin "6") (pinfunction "I6_6") (pintype "bidirectional"))
    )
    (net (code "61") (name "Net-(IC5-QD)") (class "Default")
      (node (ref "IC5") (pin "3") (pinfunction "QD_3") (pintype "tri_state"))
      (node (ref "Q1") (pin "5") (pinfunction "I5_5") (pintype "bidirectional"))
    )
    (net (code "62") (name "Net-(IC5-QE)") (class "Default")
      (node (ref "IC5") (pin "4") (pinfunction "QE_4") (pintype "tri_state"))
      (node (ref "Q1") (pin "4") (pinfunction "I4_4") (pintype "bidirectional"))
    )
    (net (code "63") (name "Net-(IC5-QF)") (class "Default")
      (node (ref "IC5") (pin "5") (pinfunction "QF_5") (pintype "tri_state"))
      (node (ref "Q1") (pin "3") (pinfunction "I3_3") (pintype "bidirectional"))
    )
    (net (code "64") (name "Net-(IC5-QG)") (class "Default")
      (node (ref "IC5") (pin "6") (pinfunction "QG_6") (pintype "tri_state"))
      (node (ref "Q1") (pin "2") (pinfunction "I2_2") (pintype "bidirectional"))
    )
    (net (code "65") (name "Net-(IC5-QH)") (class "Default")
      (node (ref "IC5") (pin "7") (pinfunction "QH_7") (pintype "tri_state"))
      (node (ref "Q1") (pin "1") (pinfunction "I1_1") (pintype "bidirectional"))
    )
    (net (code "66") (name "Net-(Q1-O1)") (class "Default")
      (node (ref "Q1") (pin "18") (pinfunction "O1_18") (pintype "bidirectional"))
      (node (ref "R1") (pin "1") (pinfunction "1_1") (pintype "passive"))
    )
    (net (code "67") (name "Net-(Q1-O2)") (class "Default")
      (node (ref "Q1") (pin "17") (pinfunction "O2_17") (pintype "bidirectional"))
      (node (ref "R2") (pin "1") (pinfunction "1_1") (pintype "passive"))
    )
    (net (code "68") (name "Net-(Q1-O3)") (class "Default")
      (node (ref "Q1") (pin "16") (pinfunction "O3_16") (pintype "bidirectional"))
      (node (ref "R3") (pin "1") (pinfunction "1_1") (pintype "passive"))
    )
    (net (code "69") (name "Net-(Q1-O4)") (class "Default")
      (node (ref "Q1") (pin "15") (pinfunction "O4_15") (pintype "bidirectional"))
      (node (ref "R4") (pin "1") (pinfunction "1_1") (pintype "passive"))
    )
    (net (code "70") (name "Net-(Q1-O5)") (class "Default")
      (node (ref "Q1") (pin "14") (pinfunction "O5_14") (pintype "bidirectional"))
      (node (ref "R5") (pin "1") (pinfunction "1_1") (pintype "passive"))
    )
    (net (code "71") (name "Net-(Q1-O6)") (class "Default")
      (node (ref "Q1") (pin "13") (pinfunction "O6_13") (pintype "bidirectional"))
      (node (ref "R6") (pin "1") (pinfunction "1_1") (pintype "passive"))
    )
    (net (code "72") (name "Net-(Q1-O7)") (class "Default")
      (node (ref "Q1") (pin "12") (pinfunction "O7_12") (pintype "bidirectional"))
      (node (ref "R7") (pin "1") (pinfunction "1_1") (pintype "passive"))
    )
    (net (code "73") (name "Net-(Q1-O8)") (class "Default")
      (node (ref "Q1") (pin "11") (pinfunction "O8_11") (pintype "bidirectional"))
      (node (ref "R8") (pin "1") (pinfunction "1_1") (pintype "passive"))
    )
    (net (code "74") (name "VCC") (class "Default")
      (node (ref "C1") (pin "1") (pinfunction "1_1") (pintype "passive"))
      (node (ref "C2") (pin "1") (pinfunction "1_1") (pintype "passive"))
      (node (ref "C3") (pin "1") (pinfunction "1_1") (pintype "passive"))
      (node (ref "C4") (pin "1") (pinfunction "1_1") (pintype "passive"))
      (node (ref "C5") (pin "1") (pinfunction "1_1") (pintype "passive"))
      (node (ref "IC1") (pin "16") (pinfunction "VCC_16") (pintype "power_in"))
      (node (ref "IC2") (pin "16") (pinfunction "VCC_16") (pintype "power_in"))
      (node (ref "IC3") (pin "16") (pinfunction "VCC_16") (pintype "power_in"))
      (node (ref "IC4") (pin "16") (pinfunction "VCC_16") (pintype "power_in"))
      (node (ref "IC5") (pin "16") (pinfunction "VCC_16") (pintype "power_in"))
      (node (ref "J1") (pin "4") (pinfunction "P4_4") (pintype "passive"))
      (node (ref "J2") (pin "4") (pinfunction "P4_4") (pintype "passive"))
      (node (ref "J3") (pin "4") (pinfunction "P4_4") (pintype "passive"))
    )
    (net (code "75") (name "unconnected-(IC5-QH'-Pad9)") (class "Default")
      (node (ref "IC5") (pin "9") (pinfunction "QH'_9") (pintype "tri_state"))
    )
    (net (code "76") (name "unconnected-(Q1-COMMON-Pad10)") (class "Default")
      (node (ref "Q1") (pin "10") (pinfunction "COMMON_10") (pintype "bidirectional"))
    )
  )
)
